# INPUT.net
KiCad netlist of a schematic drawn in Altium Designer
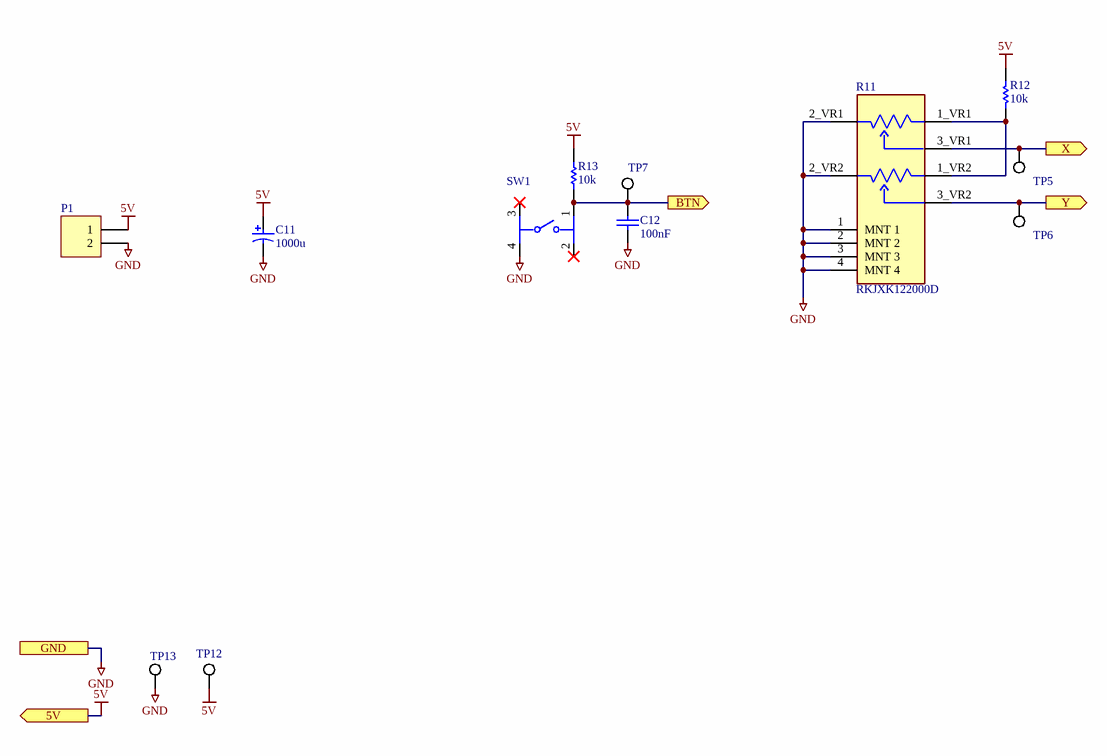
[diagram p0: INPUT.SchDoc]

(export (version "E")
  (design (tool "Eeschema 10.0.6"))
  (components
    (comp (ref "C11")
      (value "1000u")
      (footprint "NIC-CAPA2-10X10_V")
      (fields (field (name "MANUFACTURER") "Nichicon") (field (name "PARTNUMBER") "UUD1A102MNL1GS"))
      (libsource (lib "Altium Content Vault") (part "NIC-CAP-P-2"))
    )
    (comp (ref "C12")
      (value "100nF")
      (footprint "CAPC1005X56X25ML10T15")
      (fields
        (field (name "MANUFACTURER") "AVX Interconnect / Elco")
        (field (name "PART NUMBER") "0402YG104ZAT2A")
      )
      (libsource (lib "Altium Content Vault") (part "CAP"))
    )
    (comp (ref "P1")
      (value "Header 2")
      (footprint "HDR1X2")
      (description "Header, 2-Pin")
      (fields (field (name "PUBLISHER") "Altium Limited"))
      (libsource (lib "Miscellaneous Connectors") (part "Header 2"))
    )
    (comp (ref "R11")
      (value "RKJXK122000D")
      (footprint "FP-RKJXK122000D-MFG")
      (description "ALPS NAVIGATION SWITCH, RESISTIVE, PCB")
      (libsource (lib "Altium Content Vault") (part "93db0aae98ff11e5b2d55b77a9b83e2"))
    )
    (comp (ref "R12")
      (value "10k")
      (footprint "RESC1005X40X25LL05T05")
      (description "Chip Resistor, 10 KOhm, +/- 1%, 0.1 W, -55 to 155 degC, 0402 (1005 Metric), RoHS, Tape and Reel")
      (fields (field (name "TOLERANCE") "1%") (field (name "MANUFACTURER") "Panasonic"))
      (libsource (lib "Altium Content Vault") (part "RES-2"))
    )
    (comp (ref "R13")
      (value "10k")
      (footprint "RESC1005X40X25LL05T05")
      (description "Chip Resistor, 10 KOhm, +/- 1%, 0.1 W, -55 to 155 degC, 0402 (1005 Metric), RoHS, Tape and Reel")
      (fields (field (name "TOLERANCE") "1%") (field (name "MANUFACTURER") "Panasonic"))
      (libsource (lib "Altium Content Vault") (part "RES-2"))
    )
    (comp (ref "SW1")
      (value "PTS645SM43SMTR92LFS")
      (footprint "FP-PTS645SM43SMTR92LFS-MFG")
      (description "SWITCH TACTILE SPST-NO 0.05A 12V")
      (libsource (lib "Altium Content Vault") (part "1adf0dd01260c80cf25a44bfd6b99ba"))
    )
    (comp (ref "TP5")
      (value "5019")
      (footprint "KSTN-5019_V")
      (description "Test Point, 1 Position SMD, RoHS, Tape and Reel")
      (libsource (lib "Altium Content Vault") (part "TESTPOINT_WHITE"))
    )
    (comp (ref "TP6")
      (value "5019")
      (footprint "KSTN-5019_V")
      (description "Test Point, 1 Position SMD, RoHS, Tape and Reel")
      (libsource (lib "Altium Content Vault") (part "TESTPOINT_WHITE"))
    )
    (comp (ref "TP7")
      (value "5019")
      (footprint "KSTN-5019_V")
      (description "Test Point, 1 Position SMD, RoHS, Tape and Reel")
      (libsource (lib "Altium Content Vault") (part "TESTPOINT_WHITE"))
    )
    (comp (ref "TP12")
      (value "5019")
      (footprint "KSTN-5019_V")
      (description "Test Point, 1 Position SMD, RoHS, Tape and Reel")
      (libsource (lib "Altium Content Vault") (part "TESTPOINT_WHITE"))
    )
    (comp (ref "TP13")
      (value "5019")
      (footprint "KSTN-5019_V")
      (description "Test Point, 1 Position SMD, RoHS, Tape and Reel")
      (libsource (lib "Altium Content Vault") (part "TESTPOINT_WHITE"))
    )
  )
  (nets
    (net (code "1") (name "/BTN") (class "Default")
      (node (ref "C12") (pin "1") (pinfunction "1_1") (pintype "passive"))
      (node (ref "R13") (pin "1") (pinfunction "1_1") (pintype "passive"))
      (node (ref "SW1") (pin "1") (pinfunction "1_1") (pintype "passive"))
      (node (ref "TP7") (pin "1") (pinfunction "1_1") (pintype "passive"))
    )
    (net (code "2") (name "/X") (class "Default")
      (node (ref "R11") (pin "3_VR1") (pinfunction "3_VR1_3_VR1") (pintype "passive"))
      (node (ref "TP5") (pin "1") (pinfunction "1_1") (pintype "passive"))
    )
    (net (code "3") (name "/Y") (class "Default")
      (node (ref "R11") (pin "3_VR2") (pinfunction "3_VR2_3_VR2") (pintype "passive"))
      (node (ref "TP6") (pin "1") (pinfunction "1_1") (pintype "passive"))
    )
    (net (code "4") (name "5V") (class "Default")
      (node (ref "C11") (pin "1") (pinfunction "1_1") (pintype "passive"))
      (node (ref "P1") (pin "1") (pinfunction "1_1") (pintype "passive"))
      (node (ref "R12") (pin "2") (pinfunction "2_2") (pintype "passive"))
      (node (ref "R13") (pin "2") (pinfunction "2_2") (pintype "passive"))
      (node (ref "TP12") (pin "1") (pinfunction "1_1") (pintype "passive"))
    )
    (net (code "5") (name "GND") (class "Default")
      (node (ref "C11") (pin "2") (pinfunction "2_2") (pintype "passive"))
      (node (ref "C12") (pin "2") (pinfunction "2_2") (pintype "passive"))
      (node (ref "P1") (pin "2") (pinfunction "2_2") (pintype "passive"))
      (node (ref "R11") (pin "1") (pinfunction "MNT_1_1") (pintype "passive"))
      (node (ref "R11") (pin "2") (pinfunction "MNT_2_2") (pintype "passive"))
      (node (ref "R11") (pin "2_VR1") (pinfunction "2_VR1_2_VR1") (pintype "passive"))
      (node (ref "R11") (pin "2_VR2") (pinfunction "2_VR2_2_VR2") (pintype "passive"))
      (node (ref "R11") (pin "3") (pinfunction "MNT_3_3") (pintype "passive"))
      (node (ref "R11") (pin "4") (pinfunction "MNT_4_4") (pintype "passive"))
      (node (ref "SW1") (pin "4") (pinfunction "4_4") (pintype "passive"))
      (node (ref "TP13") (pin "1") (pinfunction "1_1") (pintype "passive"))
    )
    (net (code "6") (name "Net-(R11-Pad1_VR1)") (class "Default")
      (node (ref "R11") (pin "1_VR1") (pinfunction "1_VR1_1_VR1") (pintype "passive"))
      (node (ref "R11") (pin "1_VR2") (pinfunction "1_VR2_1_VR2") (pintype "passive"))
      (node (ref "R12") (pin "1") (pinfunction "1_1") (pintype "passive"))
    )
    (net (code "7") (name "unconnected-(SW1-Pad2)") (class "Default")
      (node (ref "SW1") (pin "2") (pinfunction "2_2") (pintype "passive+no_connect"))
    )
    (net (code "8") (name "unconnected-(SW1-Pad3)") (class "Default")
      (node (ref "SW1") (pin "3") (pinfunction "3_3") (pintype "passive+no_connect"))
    )
  )
)
